# design1.net
KiCad netlist of a schematic drawn in EAGLE
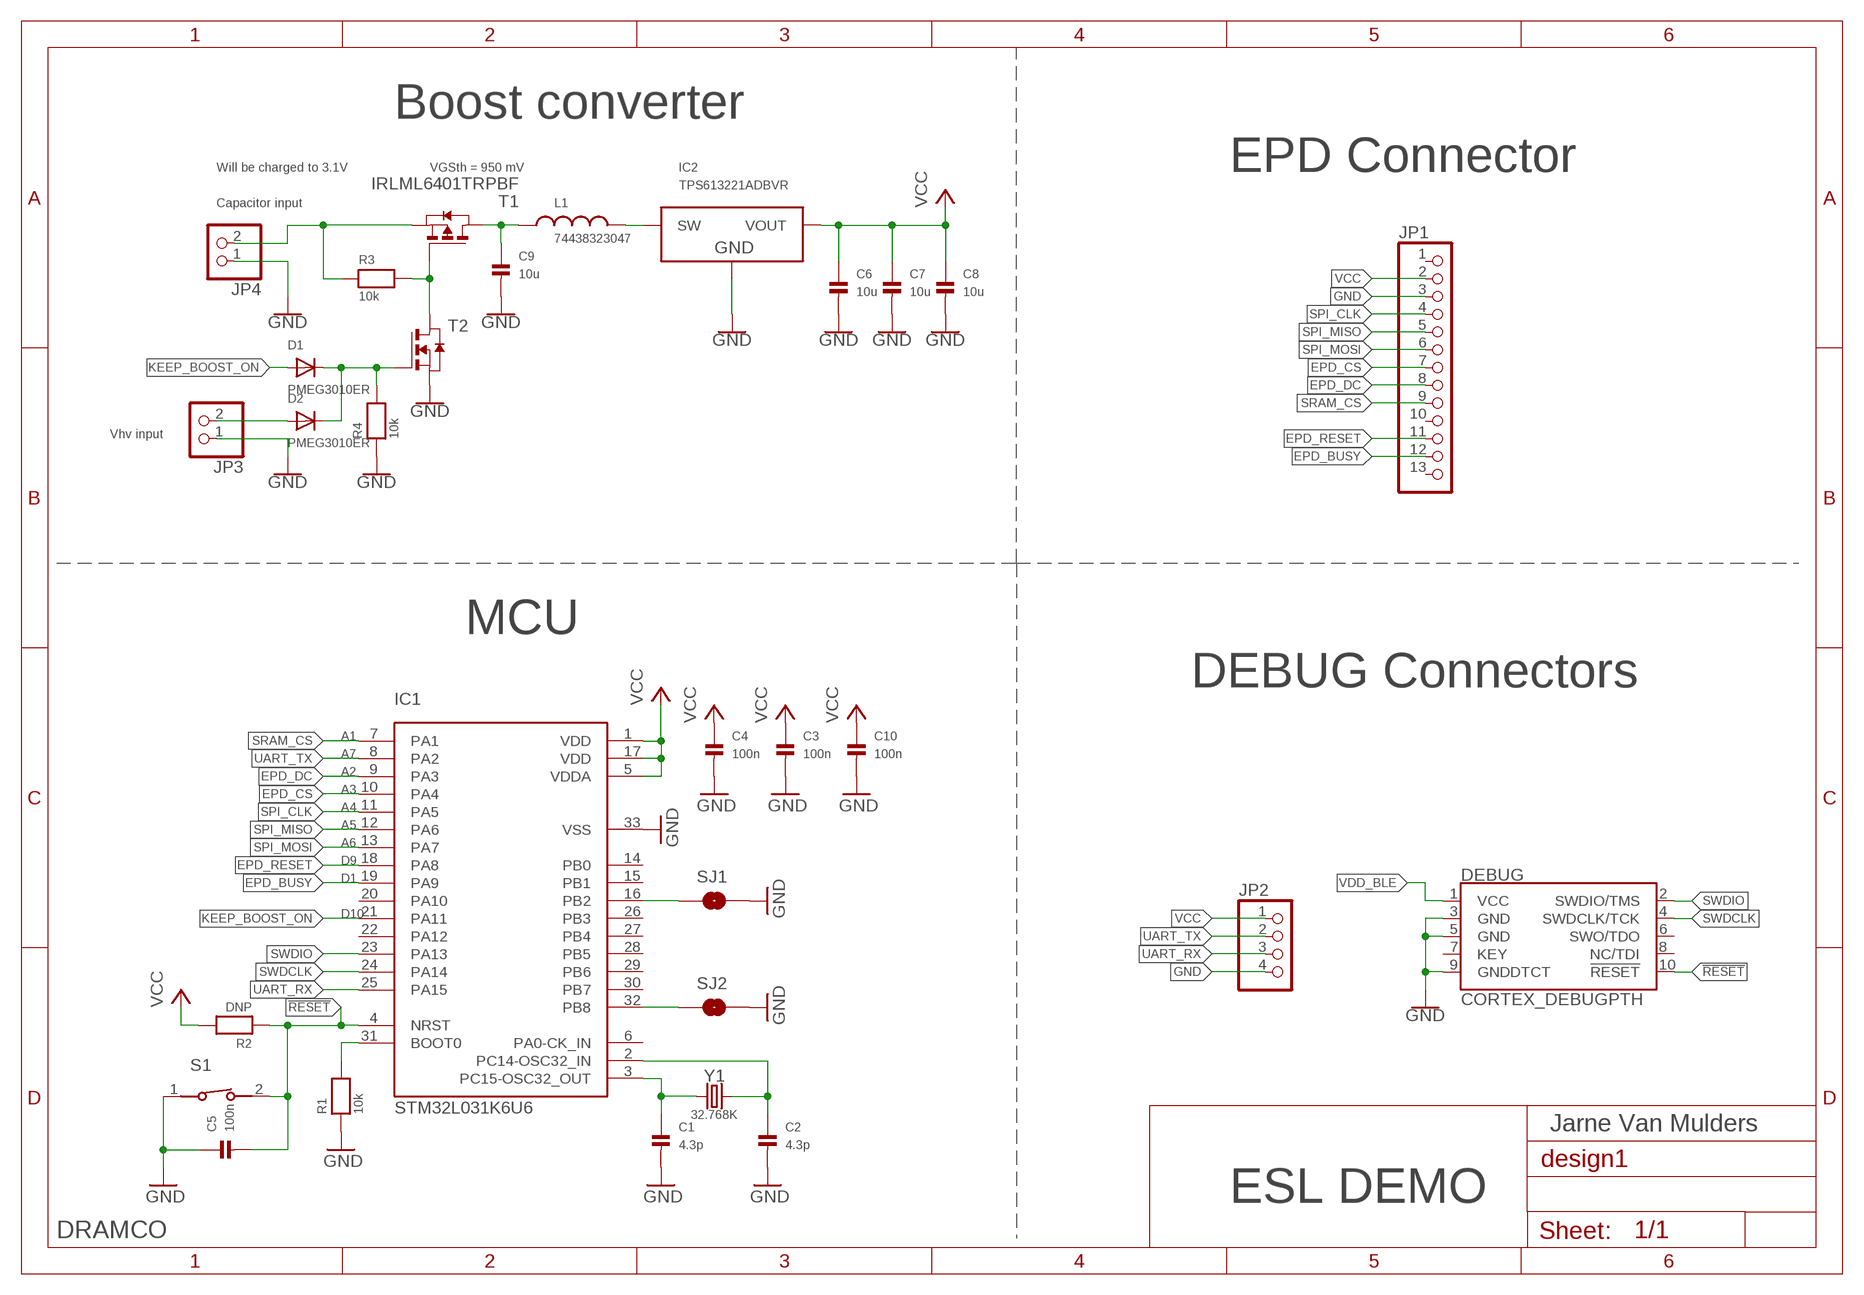
[diagram p0: schematic, sheet 1]

(export (version "E")
  (design (tool "Eeschema 10.0.6"))
  (components
    (comp (ref "C1")
      (value "4.3p")
      (footprint "eagle-import:0603")
      (libsource (lib "eagle-import") (part "CAP_CERAMIC0603"))
    )
    (comp (ref "C2")
      (value "4.3p")
      (footprint "eagle-import:0603")
      (libsource (lib "eagle-import") (part "CAP_CERAMIC0603"))
    )
    (comp (ref "C3")
      (value "100n")
      (footprint "eagle-import:0603")
      (libsource (lib "eagle-import") (part "CAP_CERAMIC0603"))
    )
    (comp (ref "C4")
      (value "100n")
      (footprint "eagle-import:0603")
      (libsource (lib "eagle-import") (part "CAP_CERAMIC0603"))
    )
    (comp (ref "C5")
      (value "100n")
      (footprint "eagle-import:0603")
      (libsource (lib "eagle-import") (part "CAP_CERAMIC0603"))
    )
    (comp (ref "C6")
      (value "10u")
      (footprint "eagle-import:0805")
      (libsource (lib "eagle-import") (part "CAP_CERAMIC0805"))
    )
    (comp (ref "C7")
      (value "10u")
      (footprint "eagle-import:0805")
      (libsource (lib "eagle-import") (part "CAP_CERAMIC0805"))
    )
    (comp (ref "C8")
      (value "10u")
      (footprint "eagle-import:0805")
      (libsource (lib "eagle-import") (part "CAP_CERAMIC0805"))
    )
    (comp (ref "C9")
      (value "10u")
      (footprint "eagle-import:0805")
      (libsource (lib "eagle-import") (part "CAP_CERAMIC0805"))
    )
    (comp (ref "C10")
      (value "100n")
      (footprint "eagle-import:0603")
      (libsource (lib "eagle-import") (part "CAP_CERAMIC0603"))
    )
    (comp (ref "D1")
      (value "PMEG3010ER")
      (footprint "eagle-import:SOD-323")
      (libsource (lib "eagle-import") (part "DIODESOD-323"))
    )
    (comp (ref "D2")
      (value "PMEG3010ER")
      (footprint "eagle-import:SOD-323")
      (libsource (lib "eagle-import") (part "DIODESOD-323"))
    )
    (comp (ref "DEBUG")
      (value "CORTEX_DEBUGPTH")
      (footprint "eagle-import:2X5-PTH-1.27MM")
      (libsource (lib "eagle-import") (part "CORTEX_DEBUGPTH"))
    )
    (comp (ref "IC1")
      (value "STM32L031K6U6")
      (footprint "eagle-import:UFQFPN32")
      (fields (field (name "MF") "STMicroelectronics"))
      (libsource (lib "eagle-import") (part "STM32L031K6U6"))
    )
    (comp (ref "IC2")
      (value "TPS61322XX")
      (footprint "eagle-import:SOT95P280X145-5N")
      (libsource (lib "eagle-import") (part "TPS61322XX"))
    )
    (comp (ref "JP1")
      (value "HEADER-1X13")
      (footprint "eagle-import:1X13_ROUND_70")
      (libsource (lib "eagle-import") (part "HEADER-1X13"))
    )
    (comp (ref "JP2")
      (value "HEADER-1X4ROUND")
      (footprint "eagle-import:1X04_ROUND")
      (libsource (lib "eagle-import") (part "HEADER-1X4ROUND"))
    )
    (comp (ref "JP3")
      (value "HEADER-1X2ROUND")
      (footprint "eagle-import:1X02_ROUND")
      (libsource (lib "eagle-import") (part "HEADER-1X2ROUND"))
    )
    (comp (ref "JP4")
      (value "HEADER-1X2ROUND")
      (footprint "eagle-import:1X02_ROUND")
      (libsource (lib "eagle-import") (part "HEADER-1X2ROUND"))
    )
    (comp (ref "L1")
      (value "74438323047")
      (footprint "eagle-import:WE-MAIA_2510")
      (libsource (lib "eagle-import") (part "WE-MAPI_2510_74438323047"))
    )
    (comp (ref "R1")
      (value "10k")
      (footprint "eagle-import:0603")
      (libsource (lib "eagle-import") (part "RESISTOR0603"))
    )
    (comp (ref "R2")
      (value "DNP")
      (footprint "eagle-import:0603")
      (libsource (lib "eagle-import") (part "RESISTOR0603"))
    )
    (comp (ref "R3")
      (value "10k")
      (footprint "eagle-import:0603")
      (libsource (lib "eagle-import") (part "RESISTOR0603"))
    )
    (comp (ref "R4")
      (value "10k")
      (footprint "eagle-import:0603")
      (libsource (lib "eagle-import") (part "RESISTOR0603"))
    )
    (comp (ref "S1")
      (value "434111043826")
      (footprint "eagle-import:434111043826")
      (libsource (lib "eagle-import") (part "434111043826"))
    )
    (comp (ref "SJ1")
      (value "SOLDERJUMPERNO")
      (footprint "eagle-import:SJ_2S-NO")
      (libsource (lib "eagle-import") (part "SOLDERJUMPERNO"))
    )
    (comp (ref "SJ2")
      (value "SOLDERJUMPERNO")
      (footprint "eagle-import:SJ_2S-NO")
      (libsource (lib "eagle-import") (part "SOLDERJUMPERNO"))
    )
    (comp (ref "T1")
      (value "IRLML6401TRPBF")
      (footprint "eagle-import:SOT-23")
      (libsource (lib "eagle-import") (part "PMOSSOT23"))
    )
    (comp (ref "T2")
      (value "NMOSSOT23")
      (footprint "eagle-import:SOT-23")
      (libsource (lib "eagle-import") (part "NMOSSOT23"))
    )
    (comp (ref "Y1")
      (value "32.768K")
      (footprint "eagle-import:CRYSTAL-SMD-3.2X1.5MM")
      (libsource (lib "eagle-import") (part "CRYSTALSMD-3.2X1.5"))
    )
  )
  (nets
    (net (code "1") (name "/~{RESET}") (class "Default")
      (node (ref "C5") (pin "2") (pinfunction "P$2_2") (pintype "passive"))
      (node (ref "DEBUG") (pin "10") (pinfunction "~{RESET}_10") (pintype "bidirectional"))
      (node (ref "IC1") (pin "4") (pinfunction "NRST_4") (pintype "bidirectional"))
      (node (ref "R2") (pin "1") (pinfunction "1_1") (pintype "passive"))
      (node (ref "S1") (pin "2") (pinfunction "2_2") (pintype "passive"))
    )
    (net (code "2") (name "EPD_BUSY") (class "Default")
      (node (ref "IC1") (pin "19") (pinfunction "PA9_19") (pintype "bidirectional"))
      (node (ref "JP1") (pin "12") (pinfunction "12_12") (pintype "passive"))
    )
    (net (code "3") (name "EPD_CS") (class "Default")
      (node (ref "IC1") (pin "10") (pinfunction "PA4_10") (pintype "bidirectional"))
      (node (ref "JP1") (pin "7") (pinfunction "7_7") (pintype "passive"))
    )
    (net (code "4") (name "EPD_DC") (class "Default")
      (node (ref "IC1") (pin "9") (pinfunction "PA3_9") (pintype "bidirectional"))
      (node (ref "JP1") (pin "8") (pinfunction "8_8") (pintype "passive"))
    )
    (net (code "5") (name "EPD_RESET") (class "Default")
      (node (ref "IC1") (pin "18") (pinfunction "PA8_18") (pintype "bidirectional"))
      (node (ref "JP1") (pin "11") (pinfunction "11_11") (pintype "passive"))
    )
    (net (code "6") (name "GND") (class "Default")
      (node (ref "C1") (pin "2") (pinfunction "P$2_2") (pintype "passive"))
      (node (ref "C10") (pin "2") (pinfunction "P$2_2") (pintype "passive"))
      (node (ref "C2") (pin "2") (pinfunction "P$2_2") (pintype "passive"))
      (node (ref "C3") (pin "2") (pinfunction "P$2_2") (pintype "passive"))
      (node (ref "C4") (pin "2") (pinfunction "P$2_2") (pintype "passive"))
      (node (ref "C5") (pin "1") (pinfunction "P$1_1") (pintype "passive"))
      (node (ref "C6") (pin "2") (pinfunction "P$2_2") (pintype "passive"))
      (node (ref "C7") (pin "2") (pinfunction "P$2_2") (pintype "passive"))
      (node (ref "C8") (pin "2") (pinfunction "P$2_2") (pintype "passive"))
      (node (ref "C9") (pin "2") (pinfunction "P$2_2") (pintype "passive"))
      (node (ref "DEBUG") (pin "3") (pinfunction "GND_3") (pintype "bidirectional"))
      (node (ref "DEBUG") (pin "5") (pinfunction "GND_5") (pintype "bidirectional"))
      (node (ref "DEBUG") (pin "9") (pinfunction "GNDDTCT_9") (pintype "bidirectional"))
      (node (ref "IC1") (pin "33") (pinfunction "VSS_33") (pintype "bidirectional"))
      (node (ref "IC2") (pin "2") (pinfunction "GND_2") (pintype "bidirectional"))
      (node (ref "JP1") (pin "3") (pinfunction "3_3") (pintype "passive"))
      (node (ref "JP2") (pin "4") (pinfunction "4_4") (pintype "passive"))
      (node (ref "JP3") (pin "1") (pinfunction "1_1") (pintype "passive"))
      (node (ref "JP4") (pin "1") (pinfunction "1_1") (pintype "passive"))
      (node (ref "R1") (pin "1") (pinfunction "1_1") (pintype "passive"))
      (node (ref "R4") (pin "1") (pinfunction "1_1") (pintype "passive"))
      (node (ref "S1") (pin "1") (pinfunction "1_1") (pintype "passive"))
      (node (ref "SJ1") (pin "2") (pinfunction "2_2") (pintype "passive"))
      (node (ref "SJ2") (pin "2") (pinfunction "2_2") (pintype "passive"))
      (node (ref "T2") (pin "2") (pinfunction "S_2") (pintype "passive"))
    )
    (net (code "7") (name "KEEP_BOOST_ON") (class "Default")
      (node (ref "D1") (pin "A") (pinfunction "A_A") (pintype "passive"))
      (node (ref "IC1") (pin "21") (pinfunction "PA11_21") (pintype "bidirectional"))
    )
    (net (code "8") (name "Net-(C1-P$1)") (class "Default")
      (node (ref "C1") (pin "1") (pinfunction "P$1_1") (pintype "passive"))
      (node (ref "IC1") (pin "3") (pinfunction "PC15-OSC32_OUT_3") (pintype "bidirectional"))
      (node (ref "Y1") (pin "P$1") (pinfunction "1_P$1") (pintype "passive"))
    )
    (net (code "9") (name "Net-(C2-P$1)") (class "Default")
      (node (ref "C2") (pin "1") (pinfunction "P$1_1") (pintype "passive"))
      (node (ref "IC1") (pin "2") (pinfunction "PC14-OSC32_IN_2") (pintype "bidirectional"))
      (node (ref "Y1") (pin "P$2") (pinfunction "2_P$2") (pintype "passive"))
    )
    (net (code "10") (name "Net-(C9-P$1)") (class "Default")
      (node (ref "C9") (pin "1") (pinfunction "P$1_1") (pintype "passive"))
      (node (ref "L1") (pin "1") (pinfunction "1_1") (pintype "passive"))
      (node (ref "T1") (pin "1") (pinfunction "D_1") (pintype "passive"))
    )
    (net (code "11") (name "Net-(D2-PadA)") (class "Default")
      (node (ref "D2") (pin "A") (pinfunction "A_A") (pintype "passive"))
      (node (ref "JP3") (pin "2") (pinfunction "2_2") (pintype "passive"))
    )
    (net (code "12") (name "Net-(IC1-BOOT0)") (class "Default")
      (node (ref "IC1") (pin "31") (pinfunction "BOOT0_31") (pintype "bidirectional"))
      (node (ref "R1") (pin "2") (pinfunction "2_2") (pintype "passive"))
    )
    (net (code "13") (name "Net-(IC1-PB2)") (class "Default")
      (node (ref "IC1") (pin "16") (pinfunction "PB2_16") (pintype "bidirectional"))
      (node (ref "SJ1") (pin "1") (pinfunction "1_1") (pintype "passive"))
    )
    (net (code "14") (name "Net-(IC1-PB8)") (class "Default")
      (node (ref "IC1") (pin "32") (pinfunction "PB8_32") (pintype "bidirectional"))
      (node (ref "SJ2") (pin "1") (pinfunction "1_1") (pintype "passive"))
    )
    (net (code "15") (name "Net-(IC2-SW)") (class "Default")
      (node (ref "IC2") (pin "1") (pinfunction "SW_1") (pintype "bidirectional"))
      (node (ref "L1") (pin "2") (pinfunction "2_2") (pintype "passive"))
    )
    (net (code "16") (name "Net-(T1-G)") (class "Default")
      (node (ref "R3") (pin "2") (pinfunction "2_2") (pintype "passive"))
      (node (ref "T1") (pin "3") (pinfunction "G_3") (pintype "passive"))
      (node (ref "T2") (pin "1") (pinfunction "D_1") (pintype "passive"))
    )
    (net (code "17") (name "Net-(T1-S)") (class "Default")
      (node (ref "JP4") (pin "2") (pinfunction "2_2") (pintype "passive"))
      (node (ref "R3") (pin "1") (pinfunction "1_1") (pintype "passive"))
      (node (ref "T1") (pin "2") (pinfunction "S_2") (pintype "passive"))
    )
    (net (code "18") (name "Net-(T2-G)") (class "Default")
      (node (ref "D1") (pin "C") (pinfunction "C_C") (pintype "passive"))
      (node (ref "D2") (pin "C") (pinfunction "C_C") (pintype "passive"))
      (node (ref "R4") (pin "2") (pinfunction "2_2") (pintype "passive"))
      (node (ref "T2") (pin "3") (pinfunction "G_3") (pintype "passive"))
    )
    (net (code "19") (name "SPI_CLK") (class "Default")
      (node (ref "IC1") (pin "11") (pinfunction "PA5_11") (pintype "bidirectional"))
      (node (ref "JP1") (pin "4") (pinfunction "4_4") (pintype "passive"))
    )
    (net (code "20") (name "SPI_MISO") (class "Default")
      (node (ref "IC1") (pin "12") (pinfunction "PA6_12") (pintype "bidirectional"))
      (node (ref "JP1") (pin "5") (pinfunction "5_5") (pintype "passive"))
    )
    (net (code "21") (name "SPI_MOSI") (class "Default")
      (node (ref "IC1") (pin "13") (pinfunction "PA7_13") (pintype "bidirectional"))
      (node (ref "JP1") (pin "6") (pinfunction "6_6") (pintype "passive"))
    )
    (net (code "22") (name "SRAM_CS") (class "Default")
      (node (ref "IC1") (pin "7") (pinfunction "PA1_7") (pintype "bidirectional"))
      (node (ref "JP1") (pin "9") (pinfunction "9_9") (pintype "passive"))
    )
    (net (code "23") (name "SWDCLK") (class "Default")
      (node (ref "DEBUG") (pin "4") (pinfunction "SWDCLK/TCK_4") (pintype "bidirectional"))
      (node (ref "IC1") (pin "24") (pinfunction "PA14_24") (pintype "bidirectional"))
    )
    (net (code "24") (name "SWDIO") (class "Default")
      (node (ref "DEBUG") (pin "2") (pinfunction "SWDIO/TMS_2") (pintype "bidirectional"))
      (node (ref "IC1") (pin "23") (pinfunction "PA13_23") (pintype "bidirectional"))
    )
    (net (code "25") (name "UART_RX") (class "Default")
      (node (ref "IC1") (pin "25") (pinfunction "PA15_25") (pintype "bidirectional"))
      (node (ref "JP2") (pin "3") (pinfunction "3_3") (pintype "passive"))
    )
    (net (code "26") (name "UART_TX") (class "Default")
      (node (ref "IC1") (pin "8") (pinfunction "PA2_8") (pintype "bidirectional"))
      (node (ref "JP2") (pin "2") (pinfunction "2_2") (pintype "passive"))
    )
    (net (code "27") (name "VCC") (class "Default")
      (node (ref "C10") (pin "1") (pinfunction "P$1_1") (pintype "passive"))
      (node (ref "C3") (pin "1") (pinfunction "P$1_1") (pintype "passive"))
      (node (ref "C4") (pin "1") (pinfunction "P$1_1") (pintype "passive"))
      (node (ref "C6") (pin "1") (pinfunction "P$1_1") (pintype "passive"))
      (node (ref "C7") (pin "1") (pinfunction "P$1_1") (pintype "passive"))
      (node (ref "C8") (pin "1") (pinfunction "P$1_1") (pintype "passive"))
      (node (ref "IC1") (pin "1") (pinfunction "VDD_1") (pintype "bidirectional"))
      (node (ref "IC1") (pin "17") (pinfunction "VDD_17") (pintype "bidirectional"))
      (node (ref "IC1") (pin "5") (pinfunction "VDDA_5") (pintype "bidirectional"))
      (node (ref "IC2") (pin "4") (pinfunction "VOUT_4") (pintype "bidirectional"))
      (node (ref "JP1") (pin "2") (pinfunction "2_2") (pintype "passive"))
      (node (ref "JP2") (pin "1") (pinfunction "1_1") (pintype "passive"))
      (node (ref "R2") (pin "2") (pinfunction "2_2") (pintype "passive"))
    )
    (net (code "28") (name "VDD_BLE") (class "Default")
      (node (ref "DEBUG") (pin "1") (pinfunction "VCC_1") (pintype "bidirectional"))
    )
    (net (code "29") (name "unconnected-(DEBUG-KEY-Pad7)") (class "Default")
      (node (ref "DEBUG") (pin "7") (pinfunction "KEY_7") (pintype "bidirectional"))
    )
    (net (code "30") (name "unconnected-(DEBUG-NC{slash}TDI-Pad8)") (class "Default")
      (node (ref "DEBUG") (pin "8") (pinfunction "NC/TDI_8") (pintype "bidirectional"))
    )
    (net (code "31") (name "unconnected-(DEBUG-SWO{slash}TDO-Pad6)") (class "Default")
      (node (ref "DEBUG") (pin "6") (pinfunction "SWO/TDO_6") (pintype "bidirectional"))
    )
    (net (code "32") (name "unconnected-(IC1-PA0-CK_IN-Pad6)") (class "Default")
      (node (ref "IC1") (pin "6") (pinfunction "PA0-CK_IN_6") (pintype "bidirectional"))
    )
    (net (code "33") (name "unconnected-(IC1-PA10-Pad20)") (class "Default")
      (node (ref "IC1") (pin "20") (pinfunction "PA10_20") (pintype "bidirectional"))
    )
    (net (code "34") (name "unconnected-(IC1-PA12-Pad22)") (class "Default")
      (node (ref "IC1") (pin "22") (pinfunction "PA12_22") (pintype "bidirectional"))
    )
    (net (code "35") (name "unconnected-(IC1-PB0-Pad14)") (class "Default")
      (node (ref "IC1") (pin "14") (pinfunction "PB0_14") (pintype "bidirectional"))
    )
    (net (code "36") (name "unconnected-(IC1-PB1-Pad15)") (class "Default")
      (node (ref "IC1") (pin "15") (pinfunction "PB1_15") (pintype "bidirectional"))
    )
    (net (code "37") (name "unconnected-(IC1-PB3-Pad26)") (class "Default")
      (node (ref "IC1") (pin "26") (pinfunction "PB3_26") (pintype "bidirectional"))
    )
    (net (code "38") (name "unconnected-(IC1-PB4-Pad27)") (class "Default")
      (node (ref "IC1") (pin "27") (pinfunction "PB4_27") (pintype "bidirectional"))
    )
    (net (code "39") (name "unconnected-(IC1-PB5-Pad28)") (class "Default")
      (node (ref "IC1") (pin "28") (pinfunction "PB5_28") (pintype "bidirectional"))
    )
    (net (code "40") (name "unconnected-(IC1-PB6-Pad29)") (class "Default")
      (node (ref "IC1") (pin "29") (pinfunction "PB6_29") (pintype "bidirectional"))
    )
    (net (code "41") (name "unconnected-(IC1-PB7-Pad30)") (class "Default")
      (node (ref "IC1") (pin "30") (pinfunction "PB7_30") (pintype "bidirectional"))
    )
    (net (code "42") (name "unconnected-(JP1-Pad1)") (class "Default")
      (node (ref "JP1") (pin "1") (pinfunction "1_1") (pintype "passive"))
    )
    (net (code "43") (name "unconnected-(JP1-Pad10)") (class "Default")
      (node (ref "JP1") (pin "10") (pinfunction "10_10") (pintype "passive"))
    )
    (net (code "44") (name "unconnected-(JP1-Pad13)") (class "Default")
      (node (ref "JP1") (pin "13") (pinfunction "13_13") (pintype "passive"))
    )
  )
)
